# 21-M2_GNSS.net
KiCad netlist of a schematic drawn in Altium Designer
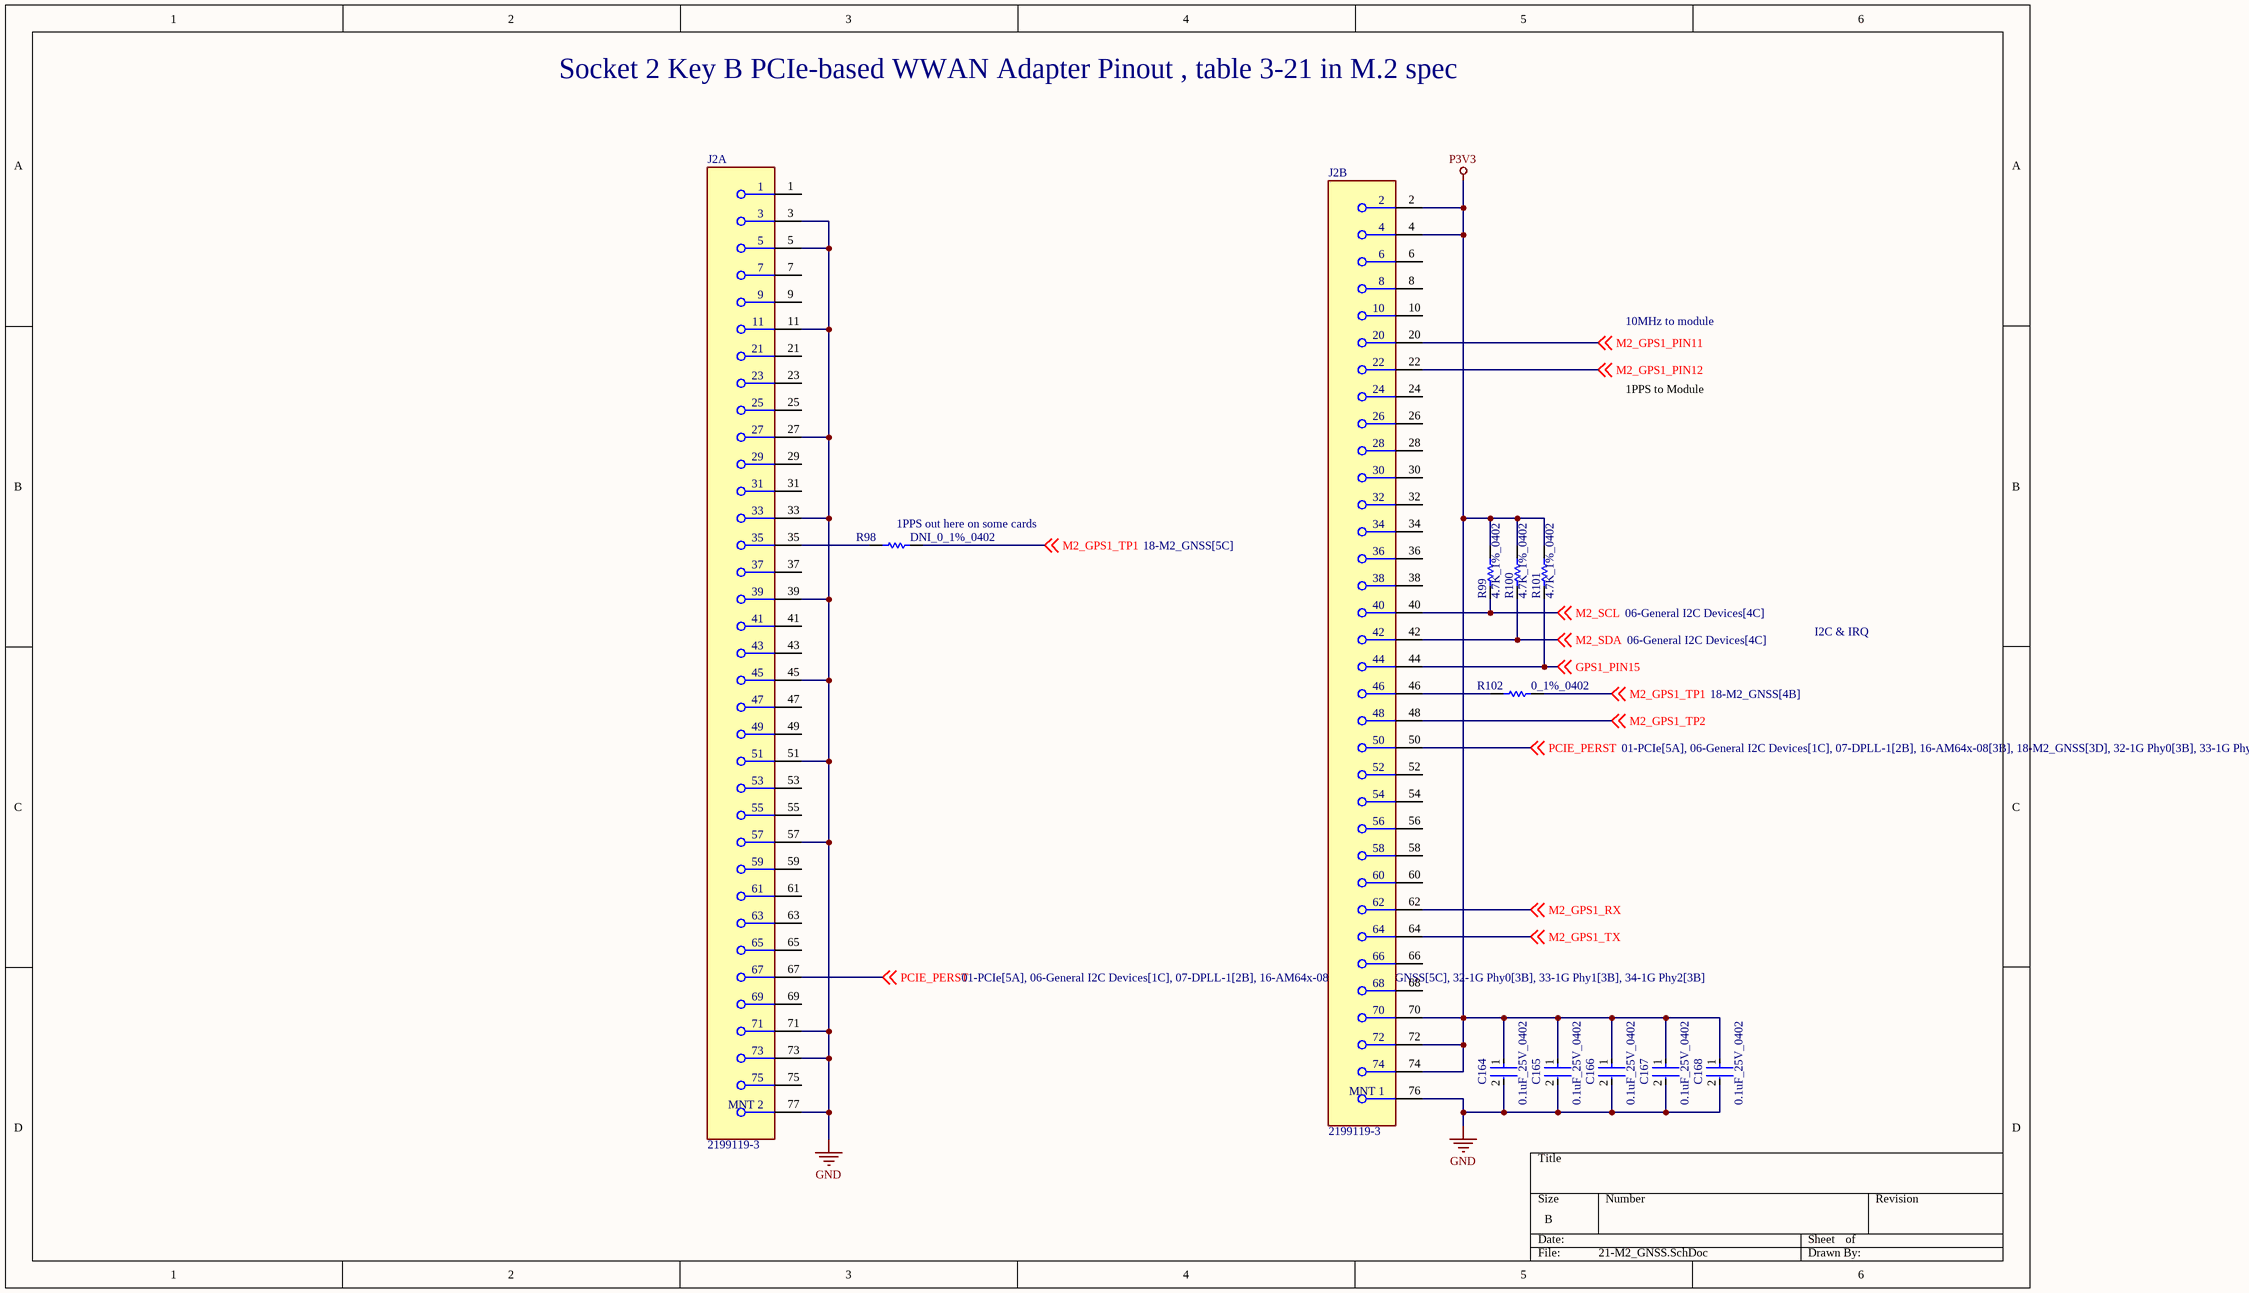
[diagram p0: 21-M2_GNSS.SchDoc]

(export (version "E")
  (design (tool "Eeschema 10.0.6"))
  (components
    (comp (ref "C164")
      (value "0.1uF_25V_0402")
      (footprint "FP-0402-L_1_0_1-W_0_5_0_1-IPC_C")
      (description "General Purpose Ceramic Capacitor, 0402, 100nF, 10%, X7R, 15%, 25V")
      (fields (field (name "VOLTAGE") "25V") (field (name "TOLERANCE") "10%"))
      (libsource (lib "Altium Content Vault") (part "b4654b650e69147ec39a6b967a45e02"))
    )
    (comp (ref "C165")
      (value "0.1uF_25V_0402")
      (footprint "FP-0402-L_1_0_1-W_0_5_0_1-IPC_C")
      (description "General Purpose Ceramic Capacitor, 0402, 100nF, 10%, X7R, 15%, 25V")
      (fields (field (name "VOLTAGE") "25V") (field (name "TOLERANCE") "10%"))
      (libsource (lib "Altium Content Vault") (part "b4654b650e69147ec39a6b967a45e02"))
    )
    (comp (ref "C166")
      (value "0.1uF_25V_0402")
      (footprint "FP-0402-L_1_0_1-W_0_5_0_1-IPC_C")
      (description "General Purpose Ceramic Capacitor, 0402, 100nF, 10%, X7R, 15%, 25V")
      (fields (field (name "VOLTAGE") "25V") (field (name "TOLERANCE") "10%"))
      (libsource (lib "Altium Content Vault") (part "b4654b650e69147ec39a6b967a45e02"))
    )
    (comp (ref "C167")
      (value "0.1uF_25V_0402")
      (footprint "FP-0402-L_1_0_1-W_0_5_0_1-IPC_C")
      (description "General Purpose Ceramic Capacitor, 0402, 100nF, 10%, X7R, 15%, 25V")
      (fields (field (name "VOLTAGE") "25V") (field (name "TOLERANCE") "10%"))
      (libsource (lib "Altium Content Vault") (part "b4654b650e69147ec39a6b967a45e02"))
    )
    (comp (ref "C168")
      (value "0.1uF_25V_0402")
      (footprint "FP-0402-L_1_0_1-W_0_5_0_1-IPC_C")
      (description "General Purpose Ceramic Capacitor, 0402, 100nF, 10%, X7R, 15%, 25V")
      (fields (field (name "VOLTAGE") "25V") (field (name "TOLERANCE") "10%"))
      (libsource (lib "Altium Content Vault") (part "b4654b650e69147ec39a6b967a45e02"))
    )
    (comp (ref "J2")
      (value "2199119-3")
      (footprint "FP-2199119-3-MFG")
      (description "CONN M.2 FEMALE 67POS 0.020 GOLD")
      (libsource (lib "Altium Content Vault") (part "a14843ccfa78e5d0b739856168502fb"))
    )
    (comp (ref "R98")
      (value "DNI_0_1%_0402")
      (footprint "RESC1005X40X25LL05T05")
      (description "Chip Resistor, 0 Ohm, 0.1 W, -55 to 155 degC, 0402 (1005 Metric), RoHS, Tape and Reel")
      (fields (field (name "MANUFACTURER") "Panasonic") (field (name "TOLERANCE") "5%"))
      (libsource (lib "Altium Content Vault") (part "RES-2"))
    )
    (comp (ref "R99")
      (value "4.7K_1%_0402")
      (footprint "RESC1005X40X25NL10T10")
      (fields (field (name "MANUFACTURER") "Bourns") (field (name "PART NUMBER") "CR0402-FX-4701GLF"))
      (libsource (lib "Altium Content Vault") (part "RES"))
    )
    (comp (ref "R100")
      (value "4.7K_1%_0402")
      (footprint "RESC1005X40X25NL10T10")
      (fields (field (name "MANUFACTURER") "Bourns") (field (name "PART NUMBER") "CR0402-FX-4701GLF"))
      (libsource (lib "Altium Content Vault") (part "RES"))
    )
    (comp (ref "R101")
      (value "4.7K_1%_0402")
      (footprint "RESC1005X40X25NL10T10")
      (fields (field (name "MANUFACTURER") "Bourns") (field (name "PART NUMBER") "CR0402-FX-4701GLF"))
      (libsource (lib "Altium Content Vault") (part "RES"))
    )
    (comp (ref "R102")
      (value "0_1%_0402")
      (footprint "RESC1005X40X25LL05T05")
      (description "Chip Resistor, 0 Ohm, 0.1 W, -55 to 155 degC, 0402 (1005 Metric), RoHS, Tape and Reel")
      (fields (field (name "MANUFACTURER") "Panasonic") (field (name "TOLERANCE") "5%"))
      (libsource (lib "Altium Content Vault") (part "RES-2"))
    )
  )
  (nets
    (net (code "1") (name "GND") (class "Default")
      (node (ref "C164") (pin "2") (pinfunction "2_2") (pintype "passive"))
      (node (ref "C165") (pin "2") (pinfunction "2_2") (pintype "passive"))
      (node (ref "C166") (pin "2") (pinfunction "2_2") (pintype "passive"))
      (node (ref "C167") (pin "2") (pinfunction "2_2") (pintype "passive"))
      (node (ref "C168") (pin "2") (pinfunction "2_2") (pintype "passive"))
      (node (ref "J2") (pin "11") (pinfunction "11_11") (pintype "passive"))
      (node (ref "J2") (pin "27") (pinfunction "27_27") (pintype "passive"))
      (node (ref "J2") (pin "3") (pinfunction "3_3") (pintype "passive"))
      (node (ref "J2") (pin "33") (pinfunction "33_33") (pintype "passive"))
      (node (ref "J2") (pin "39") (pinfunction "39_39") (pintype "passive"))
      (node (ref "J2") (pin "45") (pinfunction "45_45") (pintype "passive"))
      (node (ref "J2") (pin "5") (pinfunction "5_5") (pintype "passive"))
      (node (ref "J2") (pin "51") (pinfunction "51_51") (pintype "passive"))
      (node (ref "J2") (pin "57") (pinfunction "57_57") (pintype "passive"))
      (node (ref "J2") (pin "71") (pinfunction "71_71") (pintype "passive"))
      (node (ref "J2") (pin "73") (pinfunction "73_73") (pintype "passive"))
      (node (ref "J2") (pin "76") (pinfunction "MNT_1_76") (pintype "passive"))
      (node (ref "J2") (pin "77") (pinfunction "MNT_2_77") (pintype "passive"))
    )
    (net (code "2") (name "GPS1_PIN15") (class "Default")
      (node (ref "J2") (pin "44") (pinfunction "44_44") (pintype "passive"))
      (node (ref "R101") (pin "1") (pinfunction "1_1") (pintype "passive"))
    )
    (net (code "3") (name "M2_GPS1_PIN11") (class "Default")
      (node (ref "J2") (pin "20") (pinfunction "20_20") (pintype "passive"))
    )
    (net (code "4") (name "M2_GPS1_PIN12") (class "Default")
      (node (ref "J2") (pin "22") (pinfunction "22_22") (pintype "passive"))
    )
    (net (code "5") (name "M2_GPS1_RX") (class "Default")
      (node (ref "J2") (pin "62") (pinfunction "62_62") (pintype "passive"))
    )
    (net (code "6") (name "M2_GPS1_TP1") (class "Default")
      (node (ref "R102") (pin "2") (pinfunction "2_2") (pintype "passive"))
      (node (ref "R98") (pin "2") (pinfunction "2_2") (pintype "passive"))
    )
    (net (code "7") (name "M2_GPS1_TP2") (class "Default")
      (node (ref "J2") (pin "48") (pinfunction "48_48") (pintype "passive"))
    )
    (net (code "8") (name "M2_GPS1_TX") (class "Default")
      (node (ref "J2") (pin "64") (pinfunction "64_64") (pintype "passive"))
    )
    (net (code "9") (name "M2_SCL") (class "Default")
      (node (ref "J2") (pin "40") (pinfunction "40_40") (pintype "passive"))
      (node (ref "R99") (pin "1") (pinfunction "1_1") (pintype "passive"))
    )
    (net (code "10") (name "M2_SDA") (class "Default")
      (node (ref "J2") (pin "42") (pinfunction "42_42") (pintype "passive"))
      (node (ref "R100") (pin "1") (pinfunction "1_1") (pintype "passive"))
    )
    (net (code "11") (name "Net-(J2-Pad35)") (class "Default")
      (node (ref "J2") (pin "35") (pinfunction "35_35") (pintype "passive"))
      (node (ref "R98") (pin "1") (pinfunction "1_1") (pintype "passive"))
    )
    (net (code "12") (name "Net-(J2-Pad46)") (class "Default")
      (node (ref "J2") (pin "46") (pinfunction "46_46") (pintype "passive"))
      (node (ref "R102") (pin "1") (pinfunction "1_1") (pintype "passive"))
    )
    (net (code "13") (name "P3V3") (class "Default")
      (node (ref "C164") (pin "1") (pinfunction "1_1") (pintype "passive"))
      (node (ref "C165") (pin "1") (pinfunction "1_1") (pintype "passive"))
      (node (ref "C166") (pin "1") (pinfunction "1_1") (pintype "passive"))
      (node (ref "C167") (pin "1") (pinfunction "1_1") (pintype "passive"))
      (node (ref "C168") (pin "1") (pinfunction "1_1") (pintype "passive"))
      (node (ref "J2") (pin "2") (pinfunction "2_2") (pintype "passive"))
      (node (ref "J2") (pin "4") (pinfunction "4_4") (pintype "passive"))
      (node (ref "J2") (pin "70") (pinfunction "70_70") (pintype "passive"))
      (node (ref "J2") (pin "72") (pinfunction "72_72") (pintype "passive"))
      (node (ref "J2") (pin "74") (pinfunction "74_74") (pintype "passive"))
      (node (ref "R100") (pin "2") (pinfunction "2_2") (pintype "passive"))
      (node (ref "R101") (pin "2") (pinfunction "2_2") (pintype "passive"))
      (node (ref "R99") (pin "2") (pinfunction "2_2") (pintype "passive"))
    )
    (net (code "14") (name "PCIE_PERST") (class "Default")
      (node (ref "J2") (pin "50") (pinfunction "50_50") (pintype "passive"))
      (node (ref "J2") (pin "67") (pinfunction "67_67") (pintype "passive"))
    )
    (net (code "15") (name "unconnected-(J2-Pad1)") (class "Default")
      (node (ref "J2") (pin "1") (pinfunction "1_1") (pintype "passive"))
    )
    (net (code "16") (name "unconnected-(J2-Pad6)") (class "Default")
      (node (ref "J2") (pin "6") (pinfunction "6_6") (pintype "passive"))
    )
    (net (code "17") (name "unconnected-(J2-Pad7)") (class "Default")
      (node (ref "J2") (pin "7") (pinfunction "7_7") (pintype "passive"))
    )
    (net (code "18") (name "unconnected-(J2-Pad8)") (class "Default")
      (node (ref "J2") (pin "8") (pinfunction "8_8") (pintype "passive"))
    )
    (net (code "19") (name "unconnected-(J2-Pad9)") (class "Default")
      (node (ref "J2") (pin "9") (pinfunction "9_9") (pintype "passive"))
    )
    (net (code "20") (name "unconnected-(J2-Pad10)") (class "Default")
      (node (ref "J2") (pin "10") (pinfunction "10_10") (pintype "passive"))
    )
    (net (code "21") (name "unconnected-(J2-Pad21)") (class "Default")
      (node (ref "J2") (pin "21") (pinfunction "21_21") (pintype "passive"))
    )
    (net (code "22") (name "unconnected-(J2-Pad23)") (class "Default")
      (node (ref "J2") (pin "23") (pinfunction "23_23") (pintype "passive"))
    )
    (net (code "23") (name "unconnected-(J2-Pad24)") (class "Default")
      (node (ref "J2") (pin "24") (pinfunction "24_24") (pintype "passive"))
    )
    (net (code "24") (name "unconnected-(J2-Pad25)") (class "Default")
      (node (ref "J2") (pin "25") (pinfunction "25_25") (pintype "passive"))
    )
    (net (code "25") (name "unconnected-(J2-Pad26)") (class "Default")
      (node (ref "J2") (pin "26") (pinfunction "26_26") (pintype "passive"))
    )
    (net (code "26") (name "unconnected-(J2-Pad28)") (class "Default")
      (node (ref "J2") (pin "28") (pinfunction "28_28") (pintype "passive"))
    )
    (net (code "27") (name "unconnected-(J2-Pad29)") (class "Default")
      (node (ref "J2") (pin "29") (pinfunction "29_29") (pintype "passive"))
    )
    (net (code "28") (name "unconnected-(J2-Pad30)") (class "Default")
      (node (ref "J2") (pin "30") (pinfunction "30_30") (pintype "passive"))
    )
    (net (code "29") (name "unconnected-(J2-Pad31)") (class "Default")
      (node (ref "J2") (pin "31") (pinfunction "31_31") (pintype "passive"))
    )
    (net (code "30") (name "unconnected-(J2-Pad32)") (class "Default")
      (node (ref "J2") (pin "32") (pinfunction "32_32") (pintype "passive"))
    )
    (net (code "31") (name "unconnected-(J2-Pad34)") (class "Default")
      (node (ref "J2") (pin "34") (pinfunction "34_34") (pintype "passive"))
    )
    (net (code "32") (name "unconnected-(J2-Pad36)") (class "Default")
      (node (ref "J2") (pin "36") (pinfunction "36_36") (pintype "passive"))
    )
    (net (code "33") (name "unconnected-(J2-Pad37)") (class "Default")
      (node (ref "J2") (pin "37") (pinfunction "37_37") (pintype "passive"))
    )
    (net (code "34") (name "unconnected-(J2-Pad38)") (class "Default")
      (node (ref "J2") (pin "38") (pinfunction "38_38") (pintype "passive"))
    )
    (net (code "35") (name "unconnected-(J2-Pad41)") (class "Default")
      (node (ref "J2") (pin "41") (pinfunction "41_41") (pintype "passive"))
    )
    (net (code "36") (name "unconnected-(J2-Pad43)") (class "Default")
      (node (ref "J2") (pin "43") (pinfunction "43_43") (pintype "passive"))
    )
    (net (code "37") (name "unconnected-(J2-Pad47)") (class "Default")
      (node (ref "J2") (pin "47") (pinfunction "47_47") (pintype "passive"))
    )
    (net (code "38") (name "unconnected-(J2-Pad49)") (class "Default")
      (node (ref "J2") (pin "49") (pinfunction "49_49") (pintype "passive"))
    )
    (net (code "39") (name "unconnected-(J2-Pad52)") (class "Default")
      (node (ref "J2") (pin "52") (pinfunction "52_52") (pintype "passive"))
    )
    (net (code "40") (name "unconnected-(J2-Pad53)") (class "Default")
      (node (ref "J2") (pin "53") (pinfunction "53_53") (pintype "passive"))
    )
    (net (code "41") (name "unconnected-(J2-Pad54)") (class "Default")
      (node (ref "J2") (pin "54") (pinfunction "54_54") (pintype "passive"))
    )
    (net (code "42") (name "unconnected-(J2-Pad55)") (class "Default")
      (node (ref "J2") (pin "55") (pinfunction "55_55") (pintype "passive"))
    )
    (net (code "43") (name "unconnected-(J2-Pad56)") (class "Default")
      (node (ref "J2") (pin "56") (pinfunction "56_56") (pintype "passive"))
    )
    (net (code "44") (name "unconnected-(J2-Pad58)") (class "Default")
      (node (ref "J2") (pin "58") (pinfunction "58_58") (pintype "passive"))
    )
    (net (code "45") (name "unconnected-(J2-Pad59)") (class "Default")
      (node (ref "J2") (pin "59") (pinfunction "59_59") (pintype "passive"))
    )
    (net (code "46") (name "unconnected-(J2-Pad60)") (class "Default")
      (node (ref "J2") (pin "60") (pinfunction "60_60") (pintype "passive"))
    )
    (net (code "47") (name "unconnected-(J2-Pad61)") (class "Default")
      (node (ref "J2") (pin "61") (pinfunction "61_61") (pintype "passive"))
    )
    (net (code "48") (name "unconnected-(J2-Pad63)") (class "Default")
      (node (ref "J2") (pin "63") (pinfunction "63_63") (pintype "passive"))
    )
    (net (code "49") (name "unconnected-(J2-Pad65)") (class "Default")
      (node (ref "J2") (pin "65") (pinfunction "65_65") (pintype "passive"))
    )
    (net (code "50") (name "unconnected-(J2-Pad66)") (class "Default")
      (node (ref "J2") (pin "66") (pinfunction "66_66") (pintype "passive"))
    )
    (net (code "51") (name "unconnected-(J2-Pad68)") (class "Default")
      (node (ref "J2") (pin "68") (pinfunction "68_68") (pintype "passive"))
    )
    (net (code "52") (name "unconnected-(J2-Pad69)") (class "Default")
      (node (ref "J2") (pin "69") (pinfunction "69_69") (pintype "passive"))
    )
    (net (code "53") (name "unconnected-(J2-Pad75)") (class "Default")
      (node (ref "J2") (pin "75") (pinfunction "75_75") (pintype "passive"))
    )
  )
)
